# Esquem_tico_M_dulo_Gasolina.net
KiCad netlist of a schematic drawn in Altium Designer
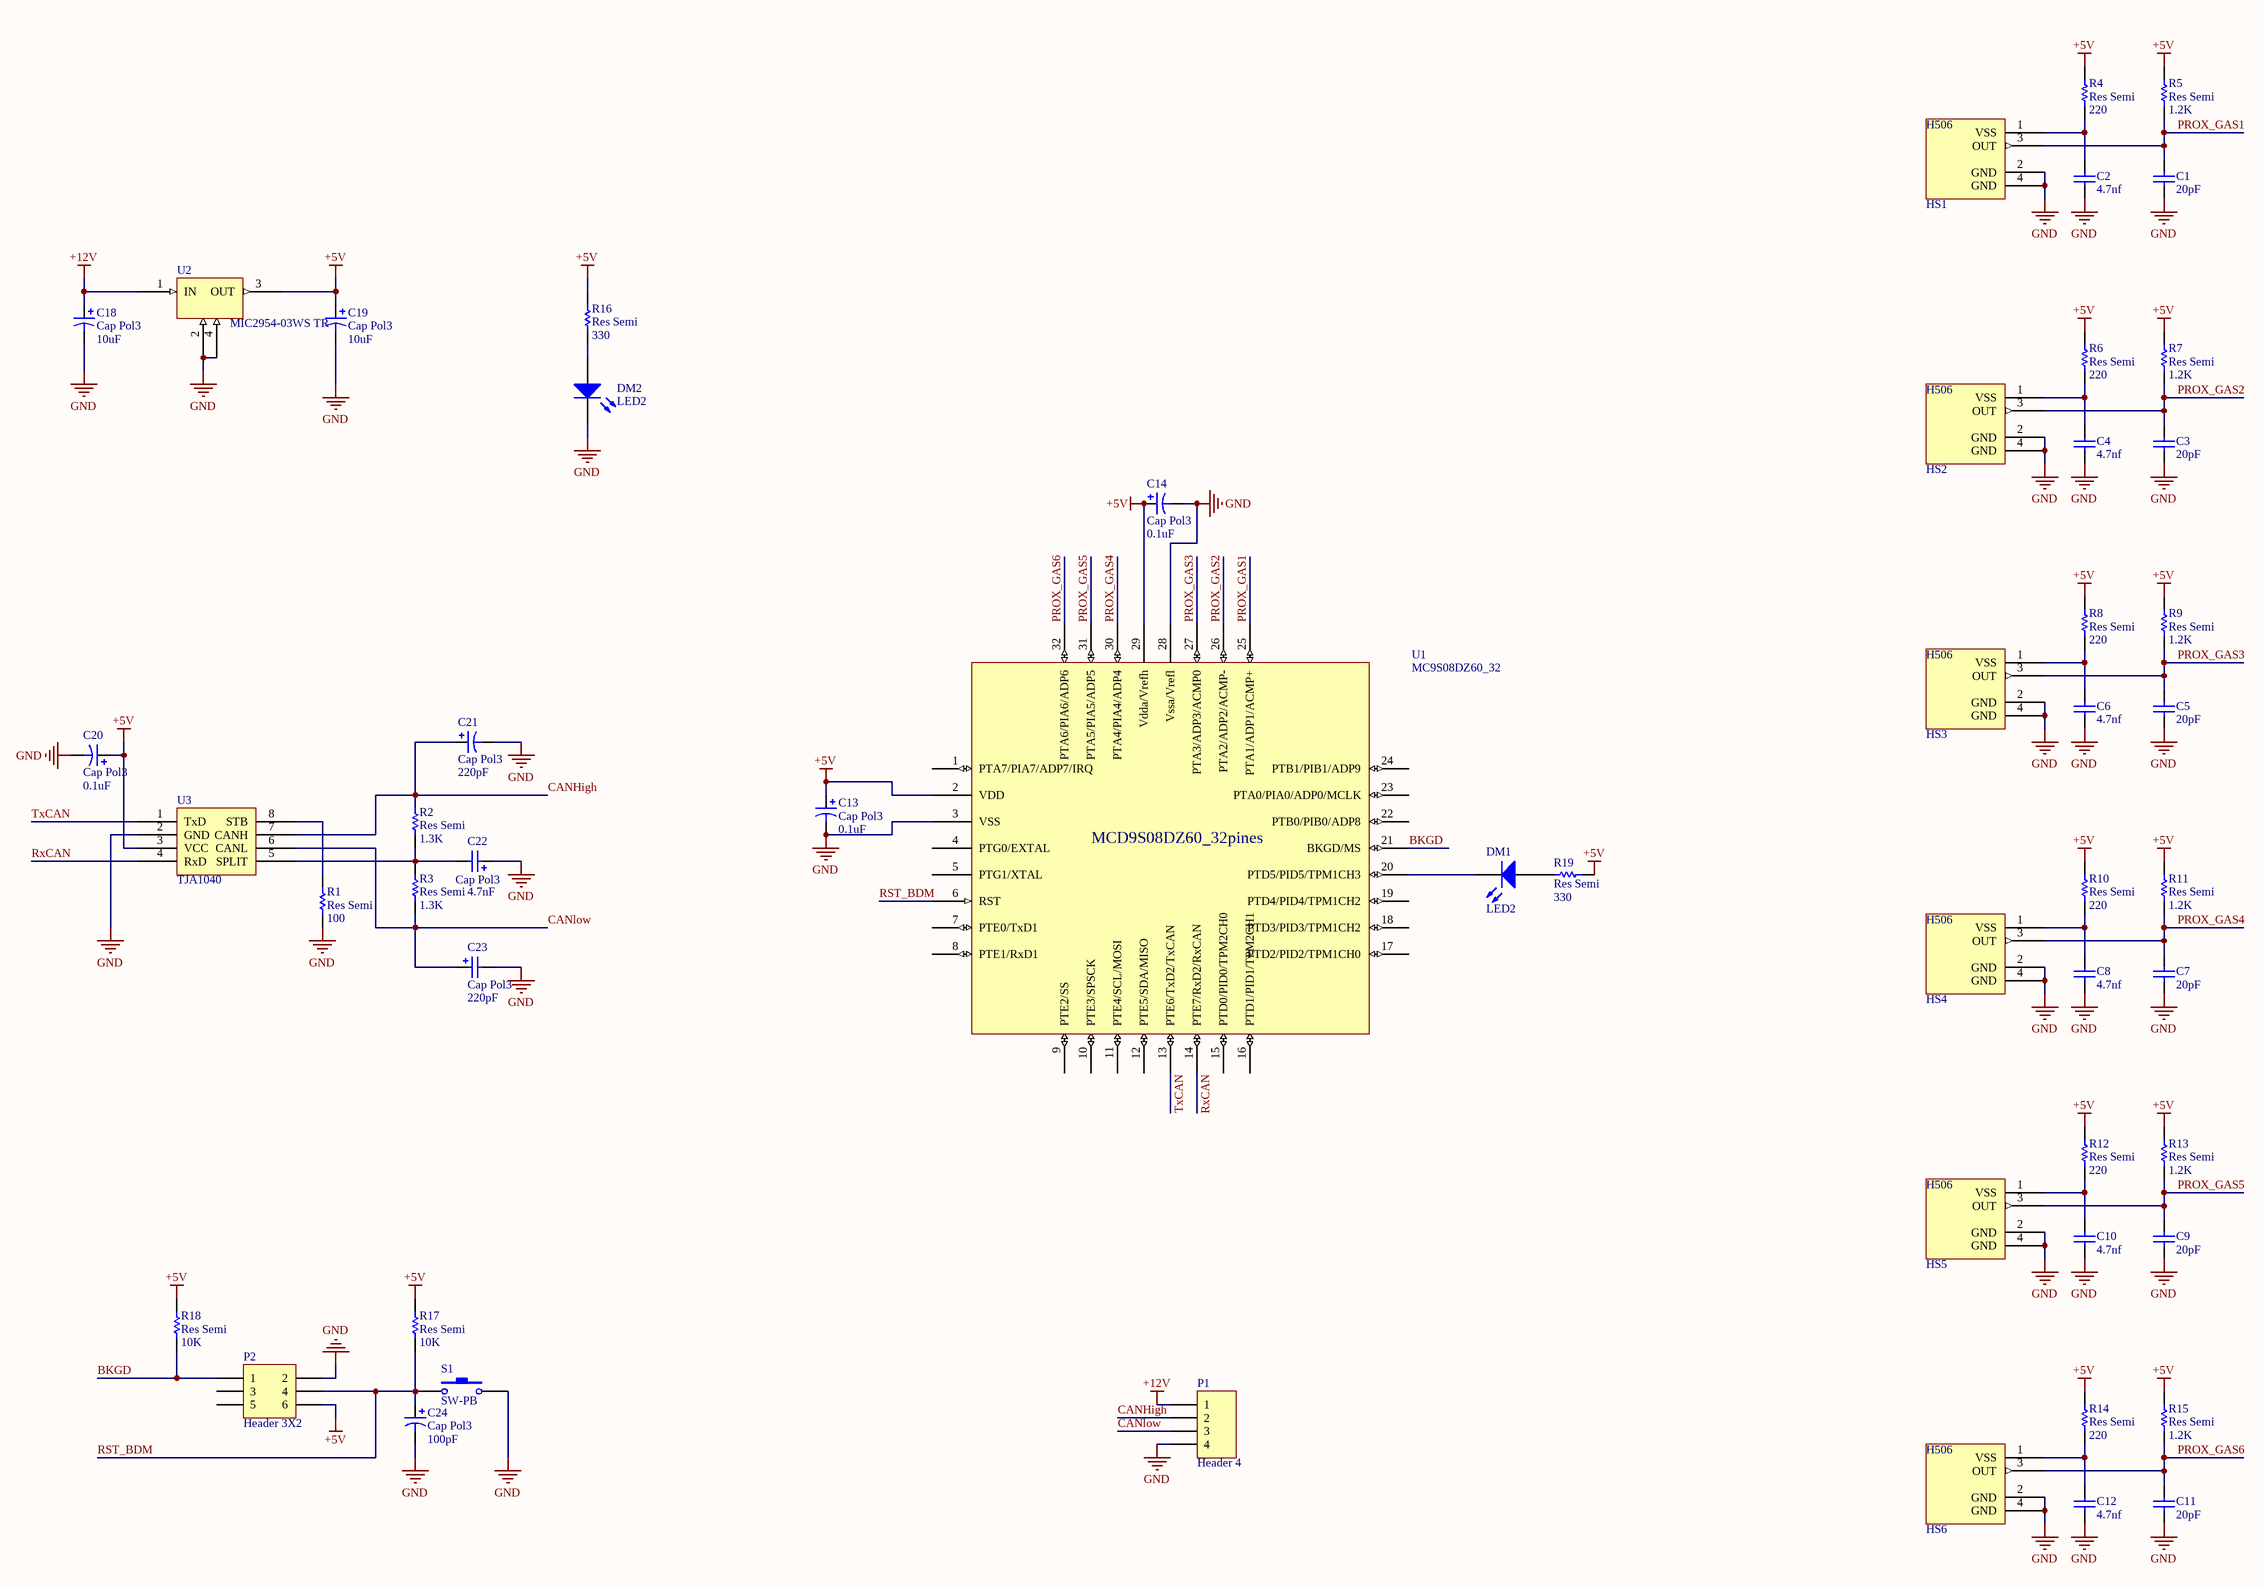
[diagram p0: Esquemático Módulo Gasolina.SchDoc]

(export (version "E")
  (design (tool "Eeschema 10.0.6"))
  (components
    (comp (ref "C1")
      (value "20pF")
      (footprint "PCB_DisplayGas:C0805")
      (description "Capacitor (Semiconductor SIM Model)")
      (fields (field (name "Comment") "Cap Semi") (field (name "PUBLISHER") "Altium Limited"))
      (libsource (lib "Miscellaneous Devices") (part "Cap Semi"))
    )
    (comp (ref "C2")
      (value "4.7nf")
      (footprint "PCB_DisplayGas:C0805")
      (description "Capacitor (Semiconductor SIM Model)")
      (fields (field (name "Comment") "Cap Semi") (field (name "PUBLISHER") "Altium Limited"))
      (libsource (lib "Miscellaneous Devices") (part "Cap Semi"))
    )
    (comp (ref "C3")
      (value "20pF")
      (footprint "PCB_DisplayGas:C0805")
      (description "Capacitor (Semiconductor SIM Model)")
      (fields (field (name "Comment") "Cap Semi") (field (name "PUBLISHER") "Altium Limited"))
      (libsource (lib "Miscellaneous Devices") (part "Cap Semi"))
    )
    (comp (ref "C4")
      (value "4.7nf")
      (footprint "PCB_DisplayGas:C0805")
      (description "Capacitor (Semiconductor SIM Model)")
      (fields (field (name "Comment") "Cap Semi") (field (name "PUBLISHER") "Altium Limited"))
      (libsource (lib "Miscellaneous Devices") (part "Cap Semi"))
    )
    (comp (ref "C5")
      (value "20pF")
      (footprint "PCB_DisplayGas:C0805")
      (description "Capacitor (Semiconductor SIM Model)")
      (fields (field (name "Comment") "Cap Semi") (field (name "PUBLISHER") "Altium Limited"))
      (libsource (lib "Miscellaneous Devices") (part "Cap Semi"))
    )
    (comp (ref "C6")
      (value "4.7nf")
      (footprint "PCB_DisplayGas:C0805")
      (description "Capacitor (Semiconductor SIM Model)")
      (fields (field (name "Comment") "Cap Semi") (field (name "PUBLISHER") "Altium Limited"))
      (libsource (lib "Miscellaneous Devices") (part "Cap Semi"))
    )
    (comp (ref "C7")
      (value "20pF")
      (footprint "PCB_DisplayGas:C0805")
      (description "Capacitor (Semiconductor SIM Model)")
      (fields (field (name "Comment") "Cap Semi") (field (name "PUBLISHER") "Altium Limited"))
      (libsource (lib "Miscellaneous Devices") (part "Cap Semi"))
    )
    (comp (ref "C8")
      (value "4.7nf")
      (footprint "PCB_DisplayGas:C0805")
      (description "Capacitor (Semiconductor SIM Model)")
      (fields (field (name "Comment") "Cap Semi") (field (name "PUBLISHER") "Altium Limited"))
      (libsource (lib "Miscellaneous Devices") (part "Cap Semi"))
    )
    (comp (ref "C9")
      (value "20pF")
      (footprint "PCB_DisplayGas:C0805")
      (description "Capacitor (Semiconductor SIM Model)")
      (fields (field (name "Comment") "Cap Semi") (field (name "PUBLISHER") "Altium Limited"))
      (libsource (lib "Miscellaneous Devices") (part "Cap Semi"))
    )
    (comp (ref "C10")
      (value "4.7nf")
      (footprint "PCB_DisplayGas:C0805")
      (description "Capacitor (Semiconductor SIM Model)")
      (fields (field (name "Comment") "Cap Semi") (field (name "PUBLISHER") "Altium Limited"))
      (libsource (lib "Miscellaneous Devices") (part "Cap Semi"))
    )
    (comp (ref "C11")
      (value "20pF")
      (footprint "PCB_DisplayGas:C0805")
      (description "Capacitor (Semiconductor SIM Model)")
      (fields (field (name "Comment") "Cap Semi") (field (name "PUBLISHER") "Altium Limited"))
      (libsource (lib "Miscellaneous Devices") (part "Cap Semi"))
    )
    (comp (ref "C12")
      (value "4.7nf")
      (footprint "PCB_DisplayGas:C0805")
      (description "Capacitor (Semiconductor SIM Model)")
      (fields (field (name "Comment") "Cap Semi") (field (name "PUBLISHER") "Altium Limited"))
      (libsource (lib "Miscellaneous Devices") (part "Cap Semi"))
    )
    (comp (ref "C13")
      (value "Cap Pol3")
      (footprint "PCB_DisplayGas:C0805")
      (description "Polarized Capacitor (Surface Mount)")
      (fields (field (name "ALTIUM_VALUE") "0.1uF") (field (name "PUBLISHER") "Altium Limited"))
      (libsource (lib "Miscellaneous Devices") (part "Cap Pol3"))
    )
    (comp (ref "C14")
      (value "Cap Pol3")
      (footprint "PCB_DisplayGas:C0805")
      (description "Polarized Capacitor (Surface Mount)")
      (fields (field (name "ALTIUM_VALUE") "0.1uF") (field (name "PUBLISHER") "Altium Limited"))
      (libsource (lib "Miscellaneous Devices") (part "Cap Pol3"))
    )
    (comp (ref "C18")
      (value "Cap Pol3")
      (footprint "PCB_DisplayGas:C0805")
      (description "Polarized Capacitor (Surface Mount)")
      (fields (field (name "ALTIUM_VALUE") "10uF") (field (name "PUBLISHER") "Altium Limited"))
      (libsource (lib "Miscellaneous Devices") (part "Cap Pol3"))
    )
    (comp (ref "C19")
      (value "Cap Pol3")
      (footprint "PCB_DisplayGas:C0805")
      (description "Polarized Capacitor (Surface Mount)")
      (fields (field (name "ALTIUM_VALUE") "10uF") (field (name "PUBLISHER") "Altium Limited"))
      (libsource (lib "Miscellaneous Devices") (part "Cap Pol3"))
    )
    (comp (ref "C20")
      (value "Cap Pol3")
      (footprint "PCB_DisplayGas:C0805")
      (description "Polarized Capacitor (Surface Mount)")
      (fields (field (name "ALTIUM_VALUE") "0.1uF") (field (name "PUBLISHER") "Altium Limited"))
      (libsource (lib "Miscellaneous Devices") (part "Cap Pol3"))
    )
    (comp (ref "C21")
      (value "Cap Pol3")
      (footprint "PCB_DisplayGas:C0805")
      (description "Polarized Capacitor (Surface Mount)")
      (fields (field (name "ALTIUM_VALUE") "220pF") (field (name "PUBLISHER") "Altium Limited"))
      (libsource (lib "Miscellaneous Devices") (part "Cap Pol3"))
    )
    (comp (ref "C22")
      (value "Cap Pol3")
      (footprint "PCB_DisplayGas:C0805")
      (description "Polarized Capacitor (Surface Mount)")
      (fields (field (name "ALTIUM_VALUE") "4.7nF") (field (name "PUBLISHER") "Altium Limited"))
      (libsource (lib "") (part "Cap Pol3_1"))
    )
    (comp (ref "C23")
      (value "Cap Pol3")
      (footprint "PCB_DisplayGas:C0805")
      (description "Polarized Capacitor (Surface Mount)")
      (fields (field (name "ALTIUM_VALUE") "220pF") (field (name "PUBLISHER") "Altium Limited"))
      (libsource (lib "") (part "Cap Pol3_1"))
    )
    (comp (ref "C24")
      (value "Cap Pol3")
      (footprint "PCB_DisplayGas:C0805")
      (description "Polarized Capacitor (Surface Mount)")
      (fields (field (name "ALTIUM_VALUE") "100pF") (field (name "PUBLISHER") "Altium Limited"))
      (libsource (lib "Miscellaneous Devices") (part "Cap Pol3"))
    )
    (comp (ref "DM1")
      (value "LED2")
      (footprint "LED SMD")
      (description "Typical RED, GREEN, YELLOW, AMBER GaAs LED")
      (fields (field (name "PUBLISHER") "Altium Limited"))
      (libsource (lib "Miscellaneous Devices") (part "LED2"))
    )
    (comp (ref "DM2")
      (value "LED2")
      (footprint "SMD pads LED")
      (description "Typical RED, GREEN, YELLOW, AMBER GaAs LED")
      (fields (field (name "PUBLISHER") "Altium Limited"))
      (libsource (lib "Miscellaneous Devices") (part "LED2"))
    )
    (comp (ref "HS1")
      (value "Component_1")
      (footprint "SOT89M")
      (libsource (lib "senssorHALLMicronas_MS") (part "Component_1"))
    )
    (comp (ref "HS2")
      (value "Component_1")
      (footprint "SOT89M")
      (libsource (lib "senssorHALLMicronas_MS") (part "Component_1"))
    )
    (comp (ref "HS3")
      (value "Component_1")
      (footprint "SOT89M")
      (libsource (lib "senssorHALLMicronas_MS") (part "Component_1"))
    )
    (comp (ref "HS4")
      (value "Component_1")
      (footprint "SOT89M")
      (libsource (lib "senssorHALLMicronas_MS") (part "Component_1"))
    )
    (comp (ref "HS5")
      (value "Component_1")
      (footprint "SOT89M")
      (libsource (lib "senssorHALLMicronas_MS") (part "Component_1"))
    )
    (comp (ref "HS6")
      (value "Component_1")
      (footprint "SOT89M")
      (libsource (lib "senssorHALLMicronas_MS") (part "Component_1"))
    )
    (comp (ref "P1")
      (value "Header 4")
      (footprint "Conector Cables 4")
      (description "Header, 4-Pin")
      (fields (field (name "PUBLISHER") "Altium Limited"))
      (libsource (lib "Miscellaneous Connectors") (part "Header 4"))
    )
    (comp (ref "P2")
      (value "Header 3X2")
      (footprint "HDR2X3 mod")
      (description "Header, 3-Pin, Dual row")
      (fields (field (name "PUBLISHER") "Altium Limited"))
      (libsource (lib "Miscellaneous Connectors") (part "Header 3X2"))
    )
    (comp (ref "R1")
      (value "Res Semi")
      (footprint "2012[0805]")
      (description "Semiconductor Resistor")
      (fields (field (name "ALTIUM_VALUE") "100") (field (name "PUBLISHER") "Altium Limited"))
      (libsource (lib "Miscellaneous Devices") (part "Res Semi"))
    )
    (comp (ref "R2")
      (value "Res Semi")
      (footprint "2012[0805]")
      (description "Semiconductor Resistor")
      (fields (field (name "ALTIUM_VALUE") "1.3K") (field (name "PUBLISHER") "Altium Limited"))
      (libsource (lib "Miscellaneous Devices") (part "Res Semi"))
    )
    (comp (ref "R3")
      (value "Res Semi")
      (footprint "2012[0805]")
      (description "Semiconductor Resistor")
      (fields (field (name "ALTIUM_VALUE") "1.3K") (field (name "PUBLISHER") "Altium Limited"))
      (libsource (lib "Miscellaneous Devices") (part "Res Semi"))
    )
    (comp (ref "R4")
      (value "Res Semi")
      (footprint "2012[0805]")
      (description "Semiconductor Resistor")
      (fields (field (name "ALTIUM_VALUE") "220") (field (name "PUBLISHER") "Altium Limited"))
      (libsource (lib "Miscellaneous Devices") (part "Res Semi"))
    )
    (comp (ref "R5")
      (value "Res Semi")
      (footprint "2012[0805]")
      (description "Semiconductor Resistor")
      (fields (field (name "ALTIUM_VALUE") "1.2K") (field (name "PUBLISHER") "Altium Limited"))
      (libsource (lib "Miscellaneous Devices") (part "Res Semi"))
    )
    (comp (ref "R6")
      (value "Res Semi")
      (footprint "2012[0805]")
      (description "Semiconductor Resistor")
      (fields (field (name "ALTIUM_VALUE") "220") (field (name "PUBLISHER") "Altium Limited"))
      (libsource (lib "Miscellaneous Devices") (part "Res Semi"))
    )
    (comp (ref "R7")
      (value "Res Semi")
      (footprint "2012[0805]")
      (description "Semiconductor Resistor")
      (fields (field (name "ALTIUM_VALUE") "1.2K") (field (name "PUBLISHER") "Altium Limited"))
      (libsource (lib "Miscellaneous Devices") (part "Res Semi"))
    )
    (comp (ref "R8")
      (value "Res Semi")
      (footprint "2012[0805]")
      (description "Semiconductor Resistor")
      (fields (field (name "ALTIUM_VALUE") "220") (field (name "PUBLISHER") "Altium Limited"))
      (libsource (lib "Miscellaneous Devices") (part "Res Semi"))
    )
    (comp (ref "R9")
      (value "Res Semi")
      (footprint "2012[0805]")
      (description "Semiconductor Resistor")
      (fields (field (name "ALTIUM_VALUE") "1.2K") (field (name "PUBLISHER") "Altium Limited"))
      (libsource (lib "Miscellaneous Devices") (part "Res Semi"))
    )
    (comp (ref "R10")
      (value "Res Semi")
      (footprint "2012[0805]")
      (description "Semiconductor Resistor")
      (fields (field (name "ALTIUM_VALUE") "220") (field (name "PUBLISHER") "Altium Limited"))
      (libsource (lib "Miscellaneous Devices") (part "Res Semi"))
    )
    (comp (ref "R11")
      (value "Res Semi")
      (footprint "2012[0805]")
      (description "Semiconductor Resistor")
      (fields (field (name "ALTIUM_VALUE") "1.2K") (field (name "PUBLISHER") "Altium Limited"))
      (libsource (lib "Miscellaneous Devices") (part "Res Semi"))
    )
    (comp (ref "R12")
      (value "Res Semi")
      (footprint "2012[0805]")
      (description "Semiconductor Resistor")
      (fields (field (name "ALTIUM_VALUE") "220") (field (name "PUBLISHER") "Altium Limited"))
      (libsource (lib "Miscellaneous Devices") (part "Res Semi"))
    )
    (comp (ref "R13")
      (value "Res Semi")
      (footprint "2012[0805]")
      (description "Semiconductor Resistor")
      (fields (field (name "ALTIUM_VALUE") "1.2K") (field (name "PUBLISHER") "Altium Limited"))
      (libsource (lib "Miscellaneous Devices") (part "Res Semi"))
    )
    (comp (ref "R14")
      (value "Res Semi")
      (footprint "2012[0805]")
      (description "Semiconductor Resistor")
      (fields (field (name "ALTIUM_VALUE") "220") (field (name "PUBLISHER") "Altium Limited"))
      (libsource (lib "Miscellaneous Devices") (part "Res Semi"))
    )
    (comp (ref "R15")
      (value "Res Semi")
      (footprint "2012[0805]")
      (description "Semiconductor Resistor")
      (fields (field (name "ALTIUM_VALUE") "1.2K") (field (name "PUBLISHER") "Altium Limited"))
      (libsource (lib "Miscellaneous Devices") (part "Res Semi"))
    )
    (comp (ref "R16")
      (value "Res Semi")
      (footprint "2012[0805]")
      (description "Semiconductor Resistor")
      (fields (field (name "ALTIUM_VALUE") "330") (field (name "PUBLISHER") "Altium Limited"))
      (libsource (lib "Miscellaneous Devices") (part "Res Semi"))
    )
    (comp (ref "R17")
      (value "Res Semi")
      (footprint "2012[0805]")
      (description "Semiconductor Resistor")
      (fields (field (name "ALTIUM_VALUE") "10K") (field (name "PUBLISHER") "Altium Limited"))
      (libsource (lib "Miscellaneous Devices") (part "Res Semi"))
    )
    (comp (ref "R18")
      (value "Res Semi")
      (footprint "2012[0805]")
      (description "Semiconductor Resistor")
      (fields (field (name "ALTIUM_VALUE") "10K") (field (name "PUBLISHER") "Altium Limited"))
      (libsource (lib "Miscellaneous Devices") (part "Res Semi"))
    )
    (comp (ref "R19")
      (value "Res Semi")
      (footprint "2012[0805]")
      (description "Semiconductor Resistor")
      (fields (field (name "ALTIUM_VALUE") "330") (field (name "PUBLISHER") "Altium Limited"))
      (libsource (lib "Miscellaneous Devices") (part "Res Semi"))
    )
    (comp (ref "S1")
      (value "SW-PB")
      (footprint "Boton")
      (description "Switch")
      (fields (field (name "PUBLISHER") "Altium Limited"))
      (libsource (lib "Miscellaneous Devices") (part "SW-PB"))
    )
    (comp (ref "U1")
      (value "MC9S08DZ60_32")
      (footprint "873-01_M")
      (libsource (lib "MC9S08DZ60MLC") (part "MC9S08DZ60_32"))
    )
    (comp (ref "U2")
      (value "MIC2954-03WS TR")
      (footprint "SOT223-4M")
      (libsource (lib "modulo_displaygas") (part "Component_1_1"))
    )
    (comp (ref "U3")
      (value "TJA1040")
      (footprint "SOT96-1_L")
      (libsource (lib "modulo_displaygas") (part "TJA1040"))
    )
  )
  (nets
    (net (code "1") (name "+5V") (class "Default")
      (node (ref "C13") (pin "1") (pinfunction "1_1") (pintype "passive"))
      (node (ref "C14") (pin "1") (pinfunction "1_1") (pintype "passive"))
      (node (ref "C19") (pin "1") (pinfunction "1_1") (pintype "passive"))
      (node (ref "C20") (pin "1") (pinfunction "1_1") (pintype "passive"))
      (node (ref "P2") (pin "6") (pinfunction "6_6") (pintype "passive"))
      (node (ref "R10") (pin "2") (pinfunction "2_2") (pintype "passive"))
      (node (ref "R11") (pin "2") (pinfunction "2_2") (pintype "passive"))
      (node (ref "R12") (pin "2") (pinfunction "2_2") (pintype "passive"))
      (node (ref "R13") (pin "2") (pinfunction "2_2") (pintype "passive"))
      (node (ref "R14") (pin "2") (pinfunction "2_2") (pintype "passive"))
      (node (ref "R15") (pin "2") (pinfunction "2_2") (pintype "passive"))
      (node (ref "R16") (pin "1") (pinfunction "1_1") (pintype "passive"))
      (node (ref "R17") (pin "2") (pinfunction "2_2") (pintype "passive"))
      (node (ref "R18") (pin "2") (pinfunction "2_2") (pintype "passive"))
      (node (ref "R19") (pin "2") (pinfunction "2_2") (pintype "passive"))
      (node (ref "R4") (pin "2") (pinfunction "2_2") (pintype "passive"))
      (node (ref "R5") (pin "2") (pinfunction "2_2") (pintype "passive"))
      (node (ref "R6") (pin "2") (pinfunction "2_2") (pintype "passive"))
      (node (ref "R7") (pin "2") (pinfunction "2_2") (pintype "passive"))
      (node (ref "R8") (pin "2") (pinfunction "2_2") (pintype "passive"))
      (node (ref "R9") (pin "2") (pinfunction "2_2") (pintype "passive"))
      (node (ref "U1") (pin "2") (pinfunction "VDD_2") (pintype "power_in"))
      (node (ref "U1") (pin "29") (pinfunction "Vdda/Vrefh_29") (pintype "power_in"))
      (node (ref "U2") (pin "3") (pinfunction "OUT_3") (pintype "output"))
      (node (ref "U3") (pin "3") (pinfunction "VCC_3") (pintype "passive"))
    )
    (net (code "2") (name "+12V") (class "Default")
      (node (ref "C18") (pin "1") (pinfunction "1_1") (pintype "passive"))
      (node (ref "P1") (pin "1") (pinfunction "1_1") (pintype "passive"))
      (node (ref "U2") (pin "1") (pinfunction "IN_1") (pintype "input"))
    )
    (net (code "3") (name "/BKGD") (class "Default")
      (node (ref "P2") (pin "1") (pinfunction "1_1") (pintype "passive"))
      (node (ref "R18") (pin "1") (pinfunction "1_1") (pintype "passive"))
      (node (ref "U1") (pin "21") (pinfunction "BKGD/MS_21") (pintype "bidirectional"))
    )
    (net (code "4") (name "/CANHigh") (class "Default")
      (node (ref "C21") (pin "1") (pinfunction "1_1") (pintype "passive"))
      (node (ref "P1") (pin "2") (pinfunction "2_2") (pintype "passive"))
      (node (ref "R2") (pin "2") (pinfunction "2_2") (pintype "passive"))
      (node (ref "U3") (pin "7") (pinfunction "CANH_7") (pintype "passive"))
    )
    (net (code "5") (name "/CANlow") (class "Default")
      (node (ref "C23") (pin "1") (pinfunction "1_1") (pintype "passive"))
      (node (ref "P1") (pin "3") (pinfunction "3_3") (pintype "passive"))
      (node (ref "R3") (pin "1") (pinfunction "1_1") (pintype "passive"))
      (node (ref "U3") (pin "6") (pinfunction "CANL_6") (pintype "passive"))
    )
    (net (code "6") (name "/PROX_GAS1") (class "Default")
      (node (ref "C1") (pin "2") (pinfunction "2_2") (pintype "passive"))
      (node (ref "HS1") (pin "3") (pinfunction "OUT_3") (pintype "output"))
      (node (ref "R5") (pin "1") (pinfunction "1_1") (pintype "passive"))
      (node (ref "U1") (pin "25") (pinfunction "PTA1/ADP1/ACMP+_25") (pintype "bidirectional"))
    )
    (net (code "7") (name "/PROX_GAS2") (class "Default")
      (node (ref "C3") (pin "2") (pinfunction "2_2") (pintype "passive"))
      (node (ref "HS2") (pin "3") (pinfunction "OUT_3") (pintype "output"))
      (node (ref "R7") (pin "1") (pinfunction "1_1") (pintype "passive"))
      (node (ref "U1") (pin "26") (pinfunction "PTA2/ADP2/ACMP-_26") (pintype "bidirectional"))
    )
    (net (code "8") (name "/PROX_GAS3") (class "Default")
      (node (ref "C5") (pin "2") (pinfunction "2_2") (pintype "passive"))
      (node (ref "HS3") (pin "3") (pinfunction "OUT_3") (pintype "output"))
      (node (ref "R9") (pin "1") (pinfunction "1_1") (pintype "passive"))
      (node (ref "U1") (pin "27") (pinfunction "PTA3/ADP3/ACMP0_27") (pintype "bidirectional"))
    )
    (net (code "9") (name "/PROX_GAS4") (class "Default")
      (node (ref "C7") (pin "2") (pinfunction "2_2") (pintype "passive"))
      (node (ref "HS4") (pin "3") (pinfunction "OUT_3") (pintype "output"))
      (node (ref "R11") (pin "1") (pinfunction "1_1") (pintype "passive"))
      (node (ref "U1") (pin "30") (pinfunction "PTA4/PIA4/ADP4_30") (pintype "bidirectional"))
    )
    (net (code "10") (name "/PROX_GAS5") (class "Default")
      (node (ref "C9") (pin "2") (pinfunction "2_2") (pintype "passive"))
      (node (ref "HS5") (pin "3") (pinfunction "OUT_3") (pintype "output"))
      (node (ref "R13") (pin "1") (pinfunction "1_1") (pintype "passive"))
      (node (ref "U1") (pin "31") (pinfunction "PTA5/PIA5/ADP5_31") (pintype "bidirectional"))
    )
    (net (code "11") (name "/PROX_GAS6") (class "Default")
      (node (ref "C11") (pin "2") (pinfunction "2_2") (pintype "passive"))
      (node (ref "HS6") (pin "3") (pinfunction "OUT_3") (pintype "output"))
      (node (ref "R15") (pin "1") (pinfunction "1_1") (pintype "passive"))
      (node (ref "U1") (pin "32") (pinfunction "PTA6/PIA6/ADP6_32") (pintype "bidirectional"))
    )
    (net (code "12") (name "/RST_BDM") (class "Default")
      (node (ref "C24") (pin "1") (pinfunction "1_1") (pintype "passive"))
      (node (ref "P2") (pin "4") (pinfunction "4_4") (pintype "passive"))
      (node (ref "R17") (pin "1") (pinfunction "1_1") (pintype "passive"))
      (node (ref "S1") (pin "1") (pinfunction "1_1") (pintype "passive"))
      (node (ref "U1") (pin "6") (pinfunction "RST_6") (pintype "input"))
    )
    (net (code "13") (name "/RxCAN") (class "Default")
      (node (ref "U1") (pin "14") (pinfunction "PTE7/RxD2/RxCAN_14") (pintype "bidirectional"))
      (node (ref "U3") (pin "4") (pinfunction "RxD_4") (pintype "passive"))
    )
    (net (code "14") (name "/TxCAN") (class "Default")
      (node (ref "U1") (pin "13") (pinfunction "PTE6/TxD2/TxCAN_13") (pintype "bidirectional"))
      (node (ref "U3") (pin "1") (pinfunction "TxD_1") (pintype "passive"))
    )
    (net (code "15") (name "GND") (class "Default")
      (node (ref "C1") (pin "1") (pinfunction "1_1") (pintype "passive"))
      (node (ref "C10") (pin "1") (pinfunction "1_1") (pintype "passive"))
      (node (ref "C11") (pin "1") (pinfunction "1_1") (pintype "passive"))
      (node (ref "C12") (pin "1") (pinfunction "1_1") (pintype "passive"))
      (node (ref "C13") (pin "2") (pinfunction "2_2") (pintype "passive"))
      (node (ref "C14") (pin "2") (pinfunction "2_2") (pintype "passive"))
      (node (ref "C18") (pin "2") (pinfunction "2_2") (pintype "passive"))
      (node (ref "C19") (pin "2") (pinfunction "2_2") (pintype "passive"))
      (node (ref "C2") (pin "1") (pinfunction "1_1") (pintype "passive"))
      (node (ref "C20") (pin "2") (pinfunction "2_2") (pintype "passive"))
      (node (ref "C21") (pin "2") (pinfunction "2_2") (pintype "passive"))
      (node (ref "C22") (pin "1") (pinfunction "1_1") (pintype "passive"))
      (node (ref "C23") (pin "2") (pinfunction "2_2") (pintype "passive"))
      (node (ref "C24") (pin "2") (pinfunction "2_2") (pintype "passive"))
      (node (ref "C3") (pin "1") (pinfunction "1_1") (pintype "passive"))
      (node (ref "C4") (pin "1") (pinfunction "1_1") (pintype "passive"))
      (node (ref "C5") (pin "1") (pinfunction "1_1") (pintype "passive"))
      (node (ref "C6") (pin "1") (pinfunction "1_1") (pintype "passive"))
      (node (ref "C7") (pin "1") (pinfunction "1_1") (pintype "passive"))
      (node (ref "C8") (pin "1") (pinfunction "1_1") (pintype "passive"))
      (node (ref "C9") (pin "1") (pinfunction "1_1") (pintype "passive"))
      (node (ref "DM2") (pin "2") (pinfunction "K_2") (pintype "passive"))
      (node (ref "HS1") (pin "2") (pinfunction "GND_2") (pintype "power_in"))
      (node (ref "HS1") (pin "4") (pinfunction "GND_4") (pintype "power_in"))
      (node (ref "HS2") (pin "2") (pinfunction "GND_2") (pintype "power_in"))
      (node (ref "HS2") (pin "4") (pinfunction "GND_4") (pintype "power_in"))
      (node (ref "HS3") (pin "2") (pinfunction "GND_2") (pintype "power_in"))
      (node (ref "HS3") (pin "4") (pinfunction "GND_4") (pintype "power_in"))
      (node (ref "HS4") (pin "2") (pinfunction "GND_2") (pintype "power_in"))
      (node (ref "HS4") (pin "4") (pinfunction "GND_4") (pintype "power_in"))
      (node (ref "HS5") (pin "2") (pinfunction "GND_2") (pintype "power_in"))
      (node (ref "HS5") (pin "4") (pinfunction "GND_4") (pintype "power_in"))
      (node (ref "HS6") (pin "2") (pinfunction "GND_2") (pintype "power_in"))
      (node (ref "HS6") (pin "4") (pinfunction "GND_4") (pintype "power_in"))
      (node (ref "P1") (pin "4") (pinfunction "4_4") (pintype "passive"))
      (node (ref "P2") (pin "2") (pinfunction "2_2") (pintype "passive"))
      (node (ref "R1") (pin "1") (pinfunction "1_1") (pintype "passive"))
      (node (ref "S1") (pin "2") (pinfunction "2_2") (pintype "passive"))
      (node (ref "U1") (pin "28") (pinfunction "Vssa/Vrefl_28") (pintype "power_in"))
      (node (ref "U1") (pin "3") (pinfunction "VSS_3") (pintype "power_in"))
      (node (ref "U2") (pin "2") (pintype "input"))
      (node (ref "U2") (pin "4") (pinfunction "13_4") (pintype "input"))
      (node (ref "U3") (pin "2") (pinfunction "GND_2") (pintype "passive"))
    )
    (net (code "16") (name "Net-(DM1-A)") (class "Default")
      (node (ref "DM1") (pin "1") (pinfunction "A_1") (pintype "passive"))
      (node (ref "R19") (pin "1") (pinfunction "1_1") (pintype "passive"))
    )
    (net (code "17") (name "Net-(DM1-K)") (class "Default")
      (node (ref "DM1") (pin "2") (pinfunction "K_2") (pintype "passive"))
      (node (ref "U1") (pin "20") (pinfunction "PTD5/PID5/TPM1CH3_20") (pintype "bidirectional"))
    )
    (net (code "18") (name "Net-(DM2-A)") (class "Default")
      (node (ref "DM2") (pin "1") (pinfunction "A_1") (pintype "passive"))
      (node (ref "R16") (pin "2") (pinfunction "2_2") (pintype "passive"))
    )
    (net (code "19") (name "Net-(HS1-VSS)") (class "Default")
      (node (ref "C2") (pin "2") (pinfunction "2_2") (pintype "passive"))
      (node (ref "HS1") (pin "1") (pinfunction "VSS_1") (pintype "power_in"))
      (node (ref "R4") (pin "1") (pinfunction "1_1") (pintype "passive"))
    )
    (net (code "20") (name "Net-(HS2-VSS)") (class "Default")
      (node (ref "C4") (pin "2") (pinfunction "2_2") (pintype "passive"))
      (node (ref "HS2") (pin "1") (pinfunction "VSS_1") (pintype "power_in"))
      (node (ref "R6") (pin "1") (pinfunction "1_1") (pintype "passive"))
    )
    (net (code "21") (name "Net-(HS3-VSS)") (class "Default")
      (node (ref "C6") (pin "2") (pinfunction "2_2") (pintype "passive"))
      (node (ref "HS3") (pin "1") (pinfunction "VSS_1") (pintype "power_in"))
      (node (ref "R8") (pin "1") (pinfunction "1_1") (pintype "passive"))
    )
    (net (code "22") (name "Net-(HS4-VSS)") (class "Default")
      (node (ref "C8") (pin "2") (pinfunction "2_2") (pintype "passive"))
      (node (ref "HS4") (pin "1") (pinfunction "VSS_1") (pintype "power_in"))
      (node (ref "R10") (pin "1") (pinfunction "1_1") (pintype "passive"))
    )
    (net (code "23") (name "Net-(HS5-VSS)") (class "Default")
      (node (ref "C10") (pin "2") (pinfunction "2_2") (pintype "passive"))
      (node (ref "HS5") (pin "1") (pinfunction "VSS_1") (pintype "power_in"))
      (node (ref "R12") (pin "1") (pinfunction "1_1") (pintype "passive"))
    )
    (net (code "24") (name "Net-(HS6-VSS)") (class "Default")
      (node (ref "C12") (pin "2") (pinfunction "2_2") (pintype "passive"))
      (node (ref "HS6") (pin "1") (pinfunction "VSS_1") (pintype "power_in"))
      (node (ref "R14") (pin "1") (pinfunction "1_1") (pintype "passive"))
    )
    (net (code "25") (name "Net-(U3-SPLIT)") (class "Default")
      (node (ref "C22") (pin "2") (pinfunction "2_2") (pintype "passive"))
      (node (ref "R2") (pin "1") (pinfunction "1_1") (pintype "passive"))
      (node (ref "R3") (pin "2") (pinfunction "2_2") (pintype "passive"))
      (node (ref "U3") (pin "5") (pinfunction "SPLIT_5") (pintype "passive"))
    )
    (net (code "26") (name "Net-(U3-STB)") (class "Default")
      (node (ref "R1") (pin "2") (pinfunction "2_2") (pintype "passive"))
      (node (ref "U3") (pin "8") (pinfunction "STB_8") (pintype "passive"))
    )
    (net (code "27") (name "unconnected-(P2-Pad3)") (class "Default")
      (node (ref "P2") (pin "3") (pinfunction "3_3") (pintype "passive"))
    )
    (net (code "28") (name "unconnected-(P2-Pad5)") (class "Default")
      (node (ref "P2") (pin "5") (pinfunction "5_5") (pintype "passive"))
    )
    (net (code "29") (name "unconnected-(U1-PTA0{slash}PIA0{slash}ADP0{slash}MCLK-Pad23)") (class "Default")
      (node (ref "U1") (pin "23") (pinfunction "PTA0/PIA0/ADP0/MCLK_23") (pintype "bidirectional"))
    )
    (net (code "30") (name "unconnected-(U1-PTA7{slash}PIA7{slash}ADP7{slash}IRQ-Pad1)") (class "Default")
      (node (ref "U1") (pin "1") (pinfunction "PTA7/PIA7/ADP7/IRQ_1") (pintype "bidirectional"))
    )
    (net (code "31") (name "unconnected-(U1-PTB0{slash}PIB0{slash}ADP8-Pad22)") (class "Default")
      (node (ref "U1") (pin "22") (pinfunction "PTB0/PIB0/ADP8_22") (pintype "bidirectional"))
    )
    (net (code "32") (name "unconnected-(U1-PTB1{slash}PIB1{slash}ADP9-Pad24)") (class "Default")
      (node (ref "U1") (pin "24") (pinfunction "PTB1/PIB1/ADP9_24") (pintype "bidirectional"))
    )
    (net (code "33") (name "unconnected-(U1-PTD0{slash}PID0{slash}TPM2CH0-Pad15)") (class "Default")
      (node (ref "U1") (pin "15") (pinfunction "PTD0/PID0/TPM2CH0_15") (pintype "bidirectional"))
    )
    (net (code "34") (name "unconnected-(U1-PTD1{slash}PID1{slash}TPM2CH1-Pad16)") (class "Default")
      (node (ref "U1") (pin "16") (pinfunction "PTD1/PID1/TPM2CH1_16") (pintype "bidirectional"))
    )
    (net (code "35") (name "unconnected-(U1-PTD2{slash}PID2{slash}TPM1CH0-Pad17)") (class "Default")
      (node (ref "U1") (pin "17") (pinfunction "PTD2/PID2/TPM1CH0_17") (pintype "bidirectional"))
    )
    (net (code "36") (name "unconnected-(U1-PTD3{slash}PID3{slash}TPM1CH2-Pad18)") (class "Default")
      (node (ref "U1") (pin "18") (pinfunction "PTD3/PID3/TPM1CH2_18") (pintype "bidirectional"))
    )
    (net (code "37") (name "unconnected-(U1-PTD4{slash}PID4{slash}TPM1CH2-Pad19)") (class "Default")
      (node (ref "U1") (pin "19") (pinfunction "PTD4/PID4/TPM1CH2_19") (pintype "bidirectional"))
    )
    (net (code "38") (name "unconnected-(U1-PTE0{slash}TxD1-Pad7)") (class "Default")
      (node (ref "U1") (pin "7") (pinfunction "PTE0/TxD1_7") (pintype "bidirectional"))
    )
    (net (code "39") (name "unconnected-(U1-PTE1{slash}RxD1-Pad8)") (class "Default")
      (node (ref "U1") (pin "8") (pinfunction "PTE1/RxD1_8") (pintype "bidirectional"))
    )
    (net (code "40") (name "unconnected-(U1-PTE2{slash}SS-Pad9)") (class "Default")
      (node (ref "U1") (pin "9") (pinfunction "PTE2/SS_9") (pintype "bidirectional"))
    )
    (net (code "41") (name "unconnected-(U1-PTE3{slash}SPSCK-Pad10)") (class "Default")
      (node (ref "U1") (pin "10") (pinfunction "PTE3/SPSCK_10") (pintype "bidirectional"))
    )
    (net (code "42") (name "unconnected-(U1-PTE4{slash}SCL{slash}MOSI-Pad11)") (class "Default")
      (node (ref "U1") (pin "11") (pinfunction "PTE4/SCL/MOSI_11") (pintype "bidirectional"))
    )
    (net (code "43") (name "unconnected-(U1-PTE5{slash}SDA{slash}MISO-Pad12)") (class "Default")
      (node (ref "U1") (pin "12") (pinfunction "PTE5/SDA/MISO_12") (pintype "bidirectional"))
    )
    (net (code "44") (name "unconnected-(U1-PTG0{slash}EXTAL-Pad4)") (class "Default")
      (node (ref "U1") (pin "4") (pinfunction "PTG0/EXTAL_4") (pintype "passive"))
    )
    (net (code "45") (name "unconnected-(U1-PTG1{slash}XTAL-Pad5)") (class "Default")
      (node (ref "U1") (pin "5") (pinfunction "PTG1/XTAL_5") (pintype "passive"))
    )
  )
)
